# GEP_Analog_Board_V100.net
KiCad netlist of a schematic drawn in EAGLE
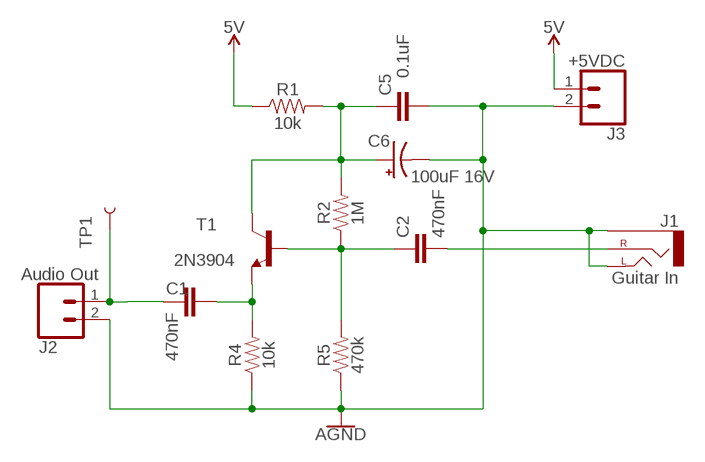
[diagram p0: schematic, sheet 1]

(export (version "E")
  (design (tool "Eeschema 10.0.6"))
  (components
    (comp (ref "C1")
      (value "470nF")
      (footprint "eagle-import:CAP-PTH-SMALL-KIT")
      (libsource (lib "eagle-import") (part "0.1UF-KIT-EZ-50V-20%"))
    )
    (comp (ref "C2")
      (value "470nF")
      (footprint "eagle-import:CAP-PTH-SMALL-KIT")
      (libsource (lib "eagle-import") (part "0.1UF-KIT-EZ-50V-20%"))
    )
    (comp (ref "C5")
      (value "0.1uF")
      (footprint "eagle-import:CAP-PTH-SMALL-KIT")
      (libsource (lib "eagle-import") (part "0.1UF-KIT-EZ-50V-20%"))
    )
    (comp (ref "C6")
      (value "100uF 16V")
      (footprint "eagle-import:CPOL-RADIAL-2.5MM-6.5MM")
      (libsource (lib "eagle-import") (part "100UF-POLAR-RADIAL-2.5MM-25V-20%"))
    )
    (comp (ref "J1")
      (value "Guitar In")
      (footprint "eagle-import:STEREOJACK2.5MM_SPECIAL_POGOPINS")
      (libsource (lib "eagle-import") (part "AUDIO_JACK_2.5MMSPECIAL_POGO_PINS"))
    )
    (comp (ref "J2")
      (value "Audio Out")
      (footprint "eagle-import:1X02")
      (libsource (lib "eagle-import") (part "CONN_02"))
    )
    (comp (ref "J3")
      (value "+5VDC")
      (footprint "eagle-import:1X02")
      (libsource (lib "eagle-import") (part "CONN_02"))
    )
    (comp (ref "R1")
      (value "10k")
      (footprint "eagle-import:AXIAL-0.3")
      (libsource (lib "eagle-import") (part "100KOHM-HORIZ-1/4W-1%"))
    )
    (comp (ref "R2")
      (value "1M")
      (footprint "eagle-import:AXIAL-0.3")
      (libsource (lib "eagle-import") (part "100KOHM-HORIZ-1/4W-1%"))
    )
    (comp (ref "R4")
      (value "10k")
      (footprint "eagle-import:AXIAL-0.3")
      (libsource (lib "eagle-import") (part "100KOHM-HORIZ-1/4W-1%"))
    )
    (comp (ref "R5")
      (value "470k")
      (footprint "eagle-import:AXIAL-0.3")
      (libsource (lib "eagle-import") (part "100KOHM-HORIZ-1/4W-1%"))
    )
    (comp (ref "T1")
      (value "2N3904")
      (footprint "eagle-import:TO92")
      (libsource (lib "eagle-import") (part "2N3904"))
    )
    (comp (ref "TP1")
      (value "TEST-POINTTP_15TH_THRU")
      (footprint "eagle-import:TP_15TH")
      (libsource (lib "eagle-import") (part "TEST-POINTTP_15TH_THRU"))
    )
  )
  (nets
    (net (code "1") (name "5V") (class "Default")
      (node (ref "J3") (pin "1") (pinfunction "1_1") (pintype "passive"))
      (node (ref "R1") (pin "P$1") (pinfunction "1_P$1") (pintype "passive"))
    )
    (net (code "2") (name "AGND") (class "Default")
      (node (ref "C5") (pin "2") (pinfunction "2_2") (pintype "passive"))
      (node (ref "C6") (pin "2") (pinfunction "-_2") (pintype "passive"))
      (node (ref "J1") (pin "RING1") (pinfunction "SLEEVE_RING1") (pintype "bidirectional"))
      (node (ref "J1") (pin "SHIELD") (pinfunction "LEFT_SHIELD") (pintype "bidirectional"))
      (node (ref "J2") (pin "2") (pinfunction "2_2") (pintype "passive"))
      (node (ref "J3") (pin "2") (pinfunction "2_2") (pintype "passive"))
      (node (ref "R4") (pin "P$1") (pinfunction "1_P$1") (pintype "passive"))
      (node (ref "R5") (pin "P$1") (pinfunction "1_P$1") (pintype "passive"))
    )
    (net (code "3") (name "Net-(C6-+)") (class "Default")
      (node (ref "C5") (pin "1") (pinfunction "1_1") (pintype "passive"))
      (node (ref "C6") (pin "1") (pinfunction "+_1") (pintype "passive"))
      (node (ref "R1") (pin "P$2") (pinfunction "2_P$2") (pintype "passive"))
      (node (ref "R2") (pin "P$2") (pinfunction "2_P$2") (pintype "passive"))
      (node (ref "T1") (pin "1") (pinfunction "C_1") (pintype "passive"))
    )
    (net (code "4") (name "Net-(J1-RIGHT)") (class "Default")
      (node (ref "C2") (pin "2") (pinfunction "2_2") (pintype "passive"))
      (node (ref "J1") (pin "TIP") (pinfunction "RIGHT_TIP") (pintype "bidirectional"))
    )
    (net (code "5") (name "Net-(R2-1)") (class "Default")
      (node (ref "C2") (pin "1") (pinfunction "1_1") (pintype "passive"))
      (node (ref "R2") (pin "P$1") (pinfunction "1_P$1") (pintype "passive"))
      (node (ref "R5") (pin "P$2") (pinfunction "2_P$2") (pintype "passive"))
      (node (ref "T1") (pin "2") (pinfunction "B_2") (pintype "passive"))
    )
    (net (code "6") (name "Net-(R4-2)") (class "Default")
      (node (ref "C1") (pin "1") (pinfunction "1_1") (pintype "passive"))
      (node (ref "R4") (pin "P$2") (pinfunction "2_P$2") (pintype "passive"))
      (node (ref "T1") (pin "3") (pinfunction "E_3") (pintype "passive"))
    )
    (net (code "7") (name "Net-(TP1-1)") (class "Default")
      (node (ref "C1") (pin "2") (pinfunction "2_2") (pintype "passive"))
      (node (ref "J2") (pin "1") (pinfunction "1_1") (pintype "passive"))
      (node (ref "TP1") (pin "P$1") (pinfunction "1_P$1") (pintype "bidirectional"))
    )
  )
)
